# ADCIN_ACcoupled_BAL-0006SMG.net
KiCad netlist of a schematic drawn in Altium Designer
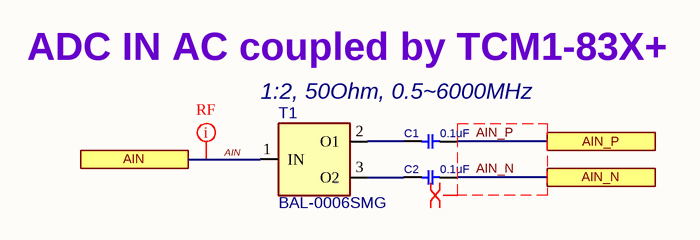
[diagram p0: ADCIN_ACcoupled_BAL-0006SMG.SchDoc]

(export (version "E")
  (design (tool "Eeschema 10.0.6"))
  (components
    (comp (ref "C1")
      (value "0.1uF")
      (footprint "C0402")
      (description "CAP, MLCC, 100nF, 50V, X7R, 10%, 0402C")
      (fields (field (name "MANF_P#") "UMK105B7104KVHF") (field (name "MANF") "Taiyo Yuden"))
      (libsource (lib "mlcc_smd_passive") (part "CAP_SMD_MLCC_100n50T"))
    )
    (comp (ref "C2")
      (value "0.1uF")
      (footprint "C0402")
      (description "CAP, MLCC, 100nF, 50V, X7R, 10%, 0402C")
      (fields (field (name "MANF_P#") "UMK105B7104KVHF") (field (name "MANF") "Taiyo Yuden"))
      (libsource (lib "mlcc_smd_passive") (part "CAP_SMD_MLCC_100n50T"))
    )
    (comp (ref "T1")
      (value "BAL-0006SMG")
      (footprint "BAL-0006SMG")
      (description "RF Transformer, 1:2, 50Ohm, 0.5~6000MHz")
      (fields (field (name "MANF") "MARKI microwave"))
      (libsource (lib "transformer_rf") (part "BAL-0006SMG"))
    )
  )
  (nets
    (net (code "1") (name "/AIN") (class "Default")
      (node (ref "T1") (pin "1") (pinfunction "IN_1") (pintype "passive"))
    )
    (net (code "2") (name "/AIN_N") (class "Default")
      (node (ref "C2") (pin "2") (pinfunction "2_2") (pintype "passive"))
    )
    (net (code "3") (name "/AIN_P") (class "Default")
      (node (ref "C1") (pin "2") (pinfunction "2_2") (pintype "passive"))
    )
    (net (code "4") (name "Net-(T1-O1)") (class "Default")
      (node (ref "C1") (pin "1") (pinfunction "1_1") (pintype "passive"))
      (node (ref "T1") (pin "2") (pinfunction "O1_2") (pintype "passive"))
    )
    (net (code "5") (name "Net-(T1-O2)") (class "Default")
      (node (ref "C2") (pin "1") (pinfunction "1_1") (pintype "passive"))
      (node (ref "T1") (pin "3") (pinfunction "O2_3") (pintype "passive"))
    )
  )
)
